# PocaFilter.net
KiCad netlist of a schematic drawn in EAGLE
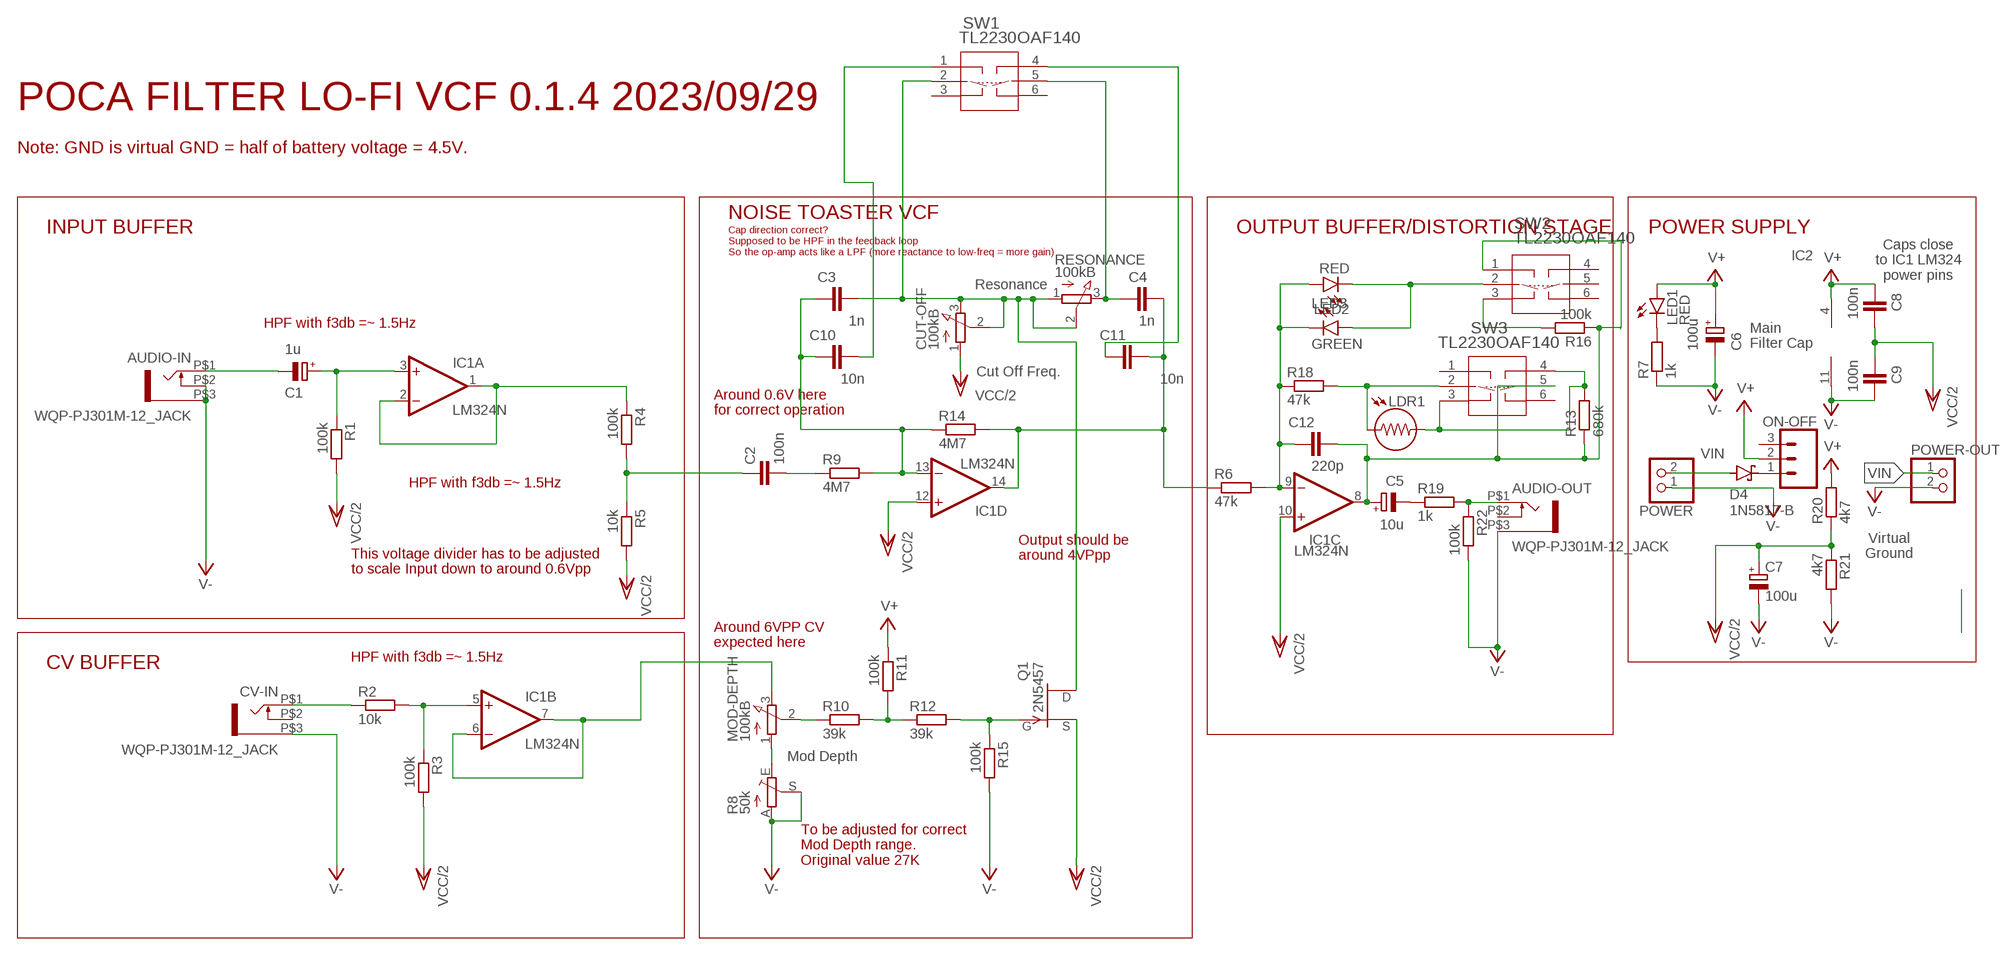
[diagram p0: schematic, sheet 1]

(export (version "E")
  (design (tool "Eeschema 10.0.6"))
  (components
    (comp (ref "AUDIO-IN")
      (value "WQP-PJ301M-12_JACK")
      (footprint "eagle-import:WQP-PJ301M-12_JACK")
      (libsource (lib "eagle-import") (part "WQP-PJ301M-12_JACK"))
    )
    (comp (ref "AUDIO-OUT")
      (value "WQP-PJ301M-12_JACK")
      (footprint "eagle-import:WQP-PJ301M-12_JACK")
      (libsource (lib "eagle-import") (part "WQP-PJ301M-12_JACK"))
    )
    (comp (ref "C1")
      (value "1u")
      (footprint "eagle-import:E2,5-6")
      (libsource (lib "eagle-import") (part "CPOL-EUE2.5-6"))
    )
    (comp (ref "C2")
      (value "100n")
      (footprint "eagle-import:C050-030X075")
      (libsource (lib "eagle-import") (part "C-EU050-030X075"))
    )
    (comp (ref "C3")
      (value "1n")
      (footprint "eagle-import:C050-030X075")
      (libsource (lib "eagle-import") (part "C-EU050-030X075"))
    )
    (comp (ref "C4")
      (value "1n")
      (footprint "eagle-import:C050-030X075")
      (libsource (lib "eagle-import") (part "C-EU050-030X075"))
    )
    (comp (ref "C5")
      (value "10u")
      (footprint "eagle-import:E2,5-6")
      (libsource (lib "eagle-import") (part "CPOL-EUE2.5-6"))
    )
    (comp (ref "C6")
      (value "100u")
      (footprint "eagle-import:E2,5-6")
      (libsource (lib "eagle-import") (part "CPOL-EUE2.5-6"))
    )
    (comp (ref "C7")
      (value "100u")
      (footprint "eagle-import:E2,5-6E")
      (libsource (lib "eagle-import") (part "CPOL-EUE2,5-6E"))
    )
    (comp (ref "C8")
      (value "100n")
      (footprint "eagle-import:C025-025X050")
      (libsource (lib "eagle-import") (part "C-EU025-025X050"))
    )
    (comp (ref "C9")
      (value "100n")
      (footprint "eagle-import:C025-025X050")
      (libsource (lib "eagle-import") (part "C-EU025-025X050"))
    )
    (comp (ref "C10")
      (value "10n")
      (footprint "eagle-import:C050-030X075")
      (libsource (lib "eagle-import") (part "C-EU050-030X075"))
    )
    (comp (ref "C11")
      (value "10n")
      (footprint "eagle-import:C050-030X075")
      (libsource (lib "eagle-import") (part "C-EU050-030X075"))
    )
    (comp (ref "C12")
      (value "220p")
      (footprint "eagle-import:C025-025X050")
      (libsource (lib "eagle-import") (part "C-EU025-025X050"))
    )
    (comp (ref "CUT-OFF")
      (value "100kB")
      (footprint "eagle-import:EVUFXM")
      (libsource (lib "eagle-import") (part "EVUMF3"))
    )
    (comp (ref "CV-IN")
      (value "WQP-PJ301M-12_JACK")
      (footprint "eagle-import:WQP-PJ301M-12_JACK")
      (libsource (lib "eagle-import") (part "WQP-PJ301M-12_JACK"))
    )
    (comp (ref "D4")
      (value "1N5817-B")
      (footprint "eagle-import:DO41-7.6")
      (libsource (lib "eagle-import") (part "1N5817-B"))
    )
    (comp (ref "IC1")
      (value "LM324N")
      (footprint "eagle-import:DIL14")
      (libsource (lib "eagle-import") (part "LM324N"))
    )
    (comp (ref "LDR1")
      (value "LDR5MM")
      (footprint "eagle-import:LDR338-54C")
      (libsource (lib "eagle-import") (part "LDR5MM"))
    )
    (comp (ref "LED1")
      (value "RED")
      (footprint "eagle-import:LED3MM")
      (libsource (lib "eagle-import") (part "led_259_LED3MM"))
    )
    (comp (ref "LED2")
      (value "RED")
      (footprint "eagle-import:LED_3MM")
      (libsource (lib "eagle-import") (part "LED3MM"))
    )
    (comp (ref "LED3")
      (value "GREEN")
      (footprint "eagle-import:LED_3MM")
      (libsource (lib "eagle-import") (part "LED3MM"))
    )
    (comp (ref "MOD-DEPTH")
      (value "100kB")
      (footprint "eagle-import:EVUFXM")
      (libsource (lib "eagle-import") (part "EVUMF3"))
    )
    (comp (ref "ON-OFF")
      (value "CONN_03LOCK")
      (footprint "eagle-import:1X03_LOCK")
      (libsource (lib "eagle-import") (part "CONN_03LOCK"))
    )
    (comp (ref "POWER")
      (value "PINHD-1X2")
      (footprint "eagle-import:1X02")
      (libsource (lib "eagle-import") (part "PINHD-1X2"))
    )
    (comp (ref "POWER-OUT")
      (value "PINHD-1X2")
      (footprint "eagle-import:1X02")
      (libsource (lib "eagle-import") (part "PINHD-1X2"))
    )
    (comp (ref "Q1")
      (value "2N5457")
      (footprint "eagle-import:TO92")
      (libsource (lib "eagle-import") (part "?20J1"))
    )
    (comp (ref "R1")
      (value "100k")
      (footprint "eagle-import:0207_10")
      (libsource (lib "eagle-import") (part "R-EU_0207/10"))
    )
    (comp (ref "R2")
      (value "10k")
      (footprint "eagle-import:0207_10")
      (libsource (lib "eagle-import") (part "R-EU_0207/10"))
    )
    (comp (ref "R3")
      (value "100k")
      (footprint "eagle-import:0207_10")
      (libsource (lib "eagle-import") (part "R-EU_0207/10"))
    )
    (comp (ref "R4")
      (value "100k")
      (footprint "eagle-import:0207_10")
      (libsource (lib "eagle-import") (part "R-EU_0207/10"))
    )
    (comp (ref "R5")
      (value "10k")
      (footprint "eagle-import:0207_10")
      (libsource (lib "eagle-import") (part "R-EU_0207/10"))
    )
    (comp (ref "R6")
      (value "47k")
      (footprint "eagle-import:0207_10")
      (libsource (lib "eagle-import") (part "R-EU_0207/10"))
    )
    (comp (ref "R7")
      (value "1k")
      (footprint "eagle-import:0207_10")
      (libsource (lib "eagle-import") (part "R-EU_0207/10"))
    )
    (comp (ref "R8")
      (value "50k")
      (footprint "eagle-import:CA6V")
      (libsource (lib "eagle-import") (part "TRIM_EU-CA6V"))
    )
    (comp (ref "R9")
      (value "4M7")
      (footprint "eagle-import:0207_10")
      (libsource (lib "eagle-import") (part "R-EU_0207/10"))
    )
    (comp (ref "R10")
      (value "39k")
      (footprint "eagle-import:0207_10")
      (libsource (lib "eagle-import") (part "R-EU_0207/10"))
    )
    (comp (ref "R11")
      (value "100k")
      (footprint "eagle-import:0207_10")
      (libsource (lib "eagle-import") (part "R-EU_0207/10"))
    )
    (comp (ref "R12")
      (value "39k")
      (footprint "eagle-import:0207_10")
      (libsource (lib "eagle-import") (part "R-EU_0207/10"))
    )
    (comp (ref "R13")
      (value "680k")
      (footprint "eagle-import:0207_10")
      (libsource (lib "eagle-import") (part "R-EU_0207/10"))
    )
    (comp (ref "R14")
      (value "4M7")
      (footprint "eagle-import:0207_10")
      (libsource (lib "eagle-import") (part "R-EU_0207/10"))
    )
    (comp (ref "R15")
      (value "100k")
      (footprint "eagle-import:0207_10")
      (libsource (lib "eagle-import") (part "R-EU_0207/10"))
    )
    (comp (ref "R16")
      (value "100k")
      (footprint "eagle-import:0204_7")
      (libsource (lib "eagle-import") (part "R-EU_0204/7"))
    )
    (comp (ref "R18")
      (value "47k")
      (footprint "eagle-import:0207_10")
      (libsource (lib "eagle-import") (part "R-EU_0207/10"))
    )
    (comp (ref "R19")
      (value "1k")
      (footprint "eagle-import:0207_10")
      (libsource (lib "eagle-import") (part "R-EU_0207/10"))
    )
    (comp (ref "R20")
      (value "4k7")
      (footprint "eagle-import:0207_10")
      (libsource (lib "eagle-import") (part "R-EU_0207/10"))
    )
    (comp (ref "R21")
      (value "4k7")
      (footprint "eagle-import:0207_10")
      (libsource (lib "eagle-import") (part "R-EU_0207/10"))
    )
    (comp (ref "R22")
      (value "100k")
      (footprint "eagle-import:0207_10")
      (libsource (lib "eagle-import") (part "R-EU_0207/10"))
    )
    (comp (ref "RESONANCE")
      (value "100kB")
      (footprint "eagle-import:EVUFXM")
      (libsource (lib "eagle-import") (part "EVUMF3"))
    )
    (comp (ref "SW1")
      (value "TL2230OAF140")
      (footprint "eagle-import:TL2230_EWI")
      (fields (field (name "COPYRIGHT") "Copyright (C) 2023 Ultra Librarian. All rights reserved."))
      (libsource (lib "eagle-import") (part "TL2230OAF140"))
    )
    (comp (ref "SW2")
      (value "TL2230OAF140")
      (footprint "eagle-import:TL2230_EWI")
      (fields (field (name "COPYRIGHT") "Copyright (C) 2023 Ultra Librarian. All rights reserved."))
      (libsource (lib "eagle-import") (part "TL2230OAF140"))
    )
    (comp (ref "SW3")
      (value "TL2230OAF140")
      (footprint "eagle-import:TL2230_EWI")
      (fields (field (name "COPYRIGHT") "Copyright (C) 2023 Ultra Librarian. All rights reserved."))
      (libsource (lib "eagle-import") (part "TL2230OAF140"))
    )
  )
  (nets
    (net (code "1") (name "Net-(AUDIO-IN-2)") (class "Default")
      (node (ref "AUDIO-IN") (pin "P$1") (pinfunction "2_P$1") (pintype "passive"))
      (node (ref "C1") (pin "-") (pinfunction "-_-") (pintype "passive"))
    )
    (net (code "2") (name "Net-(AUDIO-OUT-2)") (class "Default")
      (node (ref "AUDIO-OUT") (pin "P$1") (pinfunction "2_P$1") (pintype "passive"))
      (node (ref "R19") (pin "2") (pinfunction "2_2") (pintype "passive"))
      (node (ref "R22") (pin "1") (pinfunction "1_1") (pintype "passive"))
    )
    (net (code "3") (name "Net-(C2-Pad1)") (class "Default")
      (node (ref "C2") (pin "1") (pinfunction "1_1") (pintype "passive"))
      (node (ref "R4") (pin "2") (pinfunction "2_2") (pintype "passive"))
      (node (ref "R5") (pin "1") (pinfunction "1_1") (pintype "passive"))
    )
    (net (code "4") (name "Net-(C2-Pad2)") (class "Default")
      (node (ref "C2") (pin "2") (pinfunction "2_2") (pintype "passive"))
      (node (ref "R9") (pin "1") (pinfunction "1_1") (pintype "passive"))
    )
    (net (code "5") (name "Net-(C5-Pad-)") (class "Default")
      (node (ref "C5") (pin "-") (pinfunction "-_-") (pintype "passive"))
      (node (ref "R19") (pin "1") (pinfunction "1_1") (pintype "passive"))
    )
    (net (code "6") (name "Net-(C10-Pad2)") (class "Default")
      (node (ref "C10") (pin "2") (pinfunction "2_2") (pintype "passive"))
      (node (ref "SW1") (pin "1") (pinfunction "1_1") (pintype "passive"))
    )
    (net (code "7") (name "Net-(C11-Pad1)") (class "Default")
      (node (ref "C11") (pin "1") (pinfunction "1_1") (pintype "passive"))
      (node (ref "SW1") (pin "4") (pinfunction "4_4") (pintype "passive"))
    )
    (net (code "8") (name "Net-(CUT-OFF-E)") (class "Default")
      (node (ref "C3") (pin "2") (pinfunction "2_2") (pintype "passive"))
      (node (ref "CUT-OFF") (pin "2") (pinfunction "S_2") (pintype "passive"))
      (node (ref "CUT-OFF") (pin "3") (pinfunction "E_3") (pintype "passive"))
      (node (ref "Q1") (pin "3") (pinfunction "D_3") (pintype "passive"))
      (node (ref "RESONANCE") (pin "1") (pinfunction "A_1") (pintype "passive"))
      (node (ref "RESONANCE") (pin "2") (pinfunction "S_2") (pintype "passive"))
      (node (ref "SW1") (pin "2") (pinfunction "2_2") (pintype "passive"))
    )
    (net (code "9") (name "Net-(CV-IN-2)") (class "Default")
      (node (ref "CV-IN") (pin "P$1") (pinfunction "2_P$1") (pintype "passive"))
      (node (ref "R2") (pin "1") (pinfunction "1_1") (pintype "passive"))
    )
    (net (code "10") (name "Net-(D4-PadC)") (class "Default")
      (node (ref "D4") (pin "C") (pinfunction "C_C") (pintype "passive"))
      (node (ref "ON-OFF") (pin "1") (pinfunction "1_1") (pintype "passive"))
    )
    (net (code "11") (name "Net-(IC1A-+IN)") (class "Default")
      (node (ref "C1") (pin "+") (pinfunction "+_+") (pintype "passive"))
      (node (ref "IC1") (pin "3") (pinfunction "+IN_3") (pintype "input"))
      (node (ref "R1") (pin "1") (pinfunction "1_1") (pintype "passive"))
    )
    (net (code "12") (name "Net-(IC1A--IN)") (class "Default")
      (node (ref "IC1") (pin "1") (pinfunction "OUT_1") (pintype "output"))
      (node (ref "IC1") (pin "2") (pinfunction "-IN_2") (pintype "input"))
      (node (ref "R4") (pin "1") (pinfunction "1_1") (pintype "passive"))
    )
    (net (code "13") (name "Net-(IC1B-+IN)") (class "Default")
      (node (ref "IC1") (pin "5") (pinfunction "+IN_5") (pintype "input"))
      (node (ref "R2") (pin "2") (pinfunction "2_2") (pintype "passive"))
      (node (ref "R3") (pin "1") (pinfunction "1_1") (pintype "passive"))
    )
    (net (code "14") (name "Net-(IC1B--IN)") (class "Default")
      (node (ref "IC1") (pin "6") (pinfunction "-IN_6") (pintype "input"))
      (node (ref "IC1") (pin "7") (pinfunction "OUT_7") (pintype "output"))
      (node (ref "MOD-DEPTH") (pin "3") (pinfunction "E_3") (pintype "passive"))
    )
    (net (code "15") (name "Net-(IC1C--IN)") (class "Default")
      (node (ref "C12") (pin "1") (pinfunction "1_1") (pintype "passive"))
      (node (ref "IC1") (pin "9") (pinfunction "-IN_9") (pintype "input"))
      (node (ref "LED2") (pin "A") (pinfunction "A_A") (pintype "passive"))
      (node (ref "LED3") (pin "K") (pinfunction "C_K") (pintype "passive"))
      (node (ref "R18") (pin "1") (pinfunction "1_1") (pintype "passive"))
      (node (ref "R6") (pin "2") (pinfunction "2_2") (pintype "passive"))
    )
    (net (code "16") (name "Net-(IC1C-OUT)") (class "Default")
      (node (ref "C12") (pin "2") (pinfunction "2_2") (pintype "passive"))
      (node (ref "C5") (pin "+") (pinfunction "+_+") (pintype "passive"))
      (node (ref "IC1") (pin "8") (pinfunction "OUT_8") (pintype "output"))
      (node (ref "R13") (pin "1") (pinfunction "1_1") (pintype "passive"))
      (node (ref "R16") (pin "1") (pinfunction "1_1") (pintype "passive"))
      (node (ref "SW2") (pin "1") (pinfunction "1_1") (pintype "passive"))
      (node (ref "SW3") (pin "5") (pinfunction "5_5") (pintype "passive"))
    )
    (net (code "17") (name "Net-(IC1D--IN)") (class "Default")
      (node (ref "C10") (pin "1") (pinfunction "1_1") (pintype "passive"))
      (node (ref "C3") (pin "1") (pinfunction "1_1") (pintype "passive"))
      (node (ref "IC1") (pin "13") (pinfunction "-IN_13") (pintype "input"))
      (node (ref "R14") (pin "1") (pinfunction "1_1") (pintype "passive"))
      (node (ref "R9") (pin "2") (pinfunction "2_2") (pintype "passive"))
    )
    (net (code "18") (name "Net-(IC1D-OUT)") (class "Default")
      (node (ref "C11") (pin "2") (pinfunction "2_2") (pintype "passive"))
      (node (ref "C4") (pin "2") (pinfunction "2_2") (pintype "passive"))
      (node (ref "IC1") (pin "14") (pinfunction "OUT_14") (pintype "output"))
      (node (ref "R14") (pin "2") (pinfunction "2_2") (pintype "passive"))
      (node (ref "R6") (pin "1") (pinfunction "1_1") (pintype "passive"))
    )
    (net (code "19") (name "Net-(LDR1-Pad1)") (class "Default")
      (node (ref "LDR1") (pin "1") (pinfunction "1_1") (pintype "passive"))
      (node (ref "R18") (pin "2") (pinfunction "2_2") (pintype "passive"))
      (node (ref "SW3") (pin "2") (pinfunction "2_2") (pintype "passive"))
    )
    (net (code "20") (name "Net-(LDR1-Pad2)") (class "Default")
      (node (ref "LDR1") (pin "2") (pinfunction "2_2") (pintype "passive"))
      (node (ref "R13") (pin "2") (pinfunction "2_2") (pintype "passive"))
      (node (ref "SW3") (pin "3") (pinfunction "3_3") (pintype "passive"))
      (node (ref "SW3") (pin "4") (pinfunction "4_4") (pintype "passive"))
    )
    (net (code "21") (name "Net-(LED1-C)") (class "Default")
      (node (ref "LED1") (pin "K") (pinfunction "C_K") (pintype "passive"))
      (node (ref "R7") (pin "2") (pinfunction "2_2") (pintype "passive"))
    )
    (net (code "22") (name "Net-(LED2-C)") (class "Default")
      (node (ref "LED2") (pin "K") (pinfunction "C_K") (pintype "passive"))
      (node (ref "LED3") (pin "A") (pinfunction "A_A") (pintype "passive"))
      (node (ref "SW2") (pin "2") (pinfunction "2_2") (pintype "passive"))
    )
    (net (code "23") (name "Net-(MOD-DEPTH-A)") (class "Default")
      (node (ref "MOD-DEPTH") (pin "1") (pinfunction "A_1") (pintype "passive"))
      (node (ref "R8") (pin "E") (pinfunction "E_E") (pintype "passive"))
    )
    (net (code "24") (name "Net-(MOD-DEPTH-S)") (class "Default")
      (node (ref "MOD-DEPTH") (pin "2") (pinfunction "S_2") (pintype "passive"))
      (node (ref "R10") (pin "1") (pinfunction "1_1") (pintype "passive"))
    )
    (net (code "25") (name "Net-(Q1-G)") (class "Default")
      (node (ref "Q1") (pin "1") (pinfunction "G_1") (pintype "passive"))
      (node (ref "R12") (pin "2") (pinfunction "2_2") (pintype "passive"))
      (node (ref "R15") (pin "1") (pinfunction "1_1") (pintype "passive"))
    )
    (net (code "26") (name "Net-(R10-Pad2)") (class "Default")
      (node (ref "R10") (pin "2") (pinfunction "2_2") (pintype "passive"))
      (node (ref "R11") (pin "2") (pinfunction "2_2") (pintype "passive"))
      (node (ref "R12") (pin "1") (pinfunction "1_1") (pintype "passive"))
    )
    (net (code "27") (name "Net-(R16-Pad2)") (class "Default")
      (node (ref "R16") (pin "2") (pinfunction "2_2") (pintype "passive"))
      (node (ref "SW2") (pin "3") (pinfunction "3_3") (pintype "passive"))
    )
    (net (code "28") (name "Net-(RESONANCE-E)") (class "Default")
      (node (ref "C4") (pin "1") (pinfunction "1_1") (pintype "passive"))
      (node (ref "RESONANCE") (pin "3") (pinfunction "E_3") (pintype "passive"))
      (node (ref "SW1") (pin "5") (pinfunction "5_5") (pintype "passive"))
    )
    (net (code "29") (name "V+") (class "Default")
      (node (ref "C6") (pin "+") (pinfunction "+_+") (pintype "passive"))
      (node (ref "C8") (pin "1") (pinfunction "1_1") (pintype "passive"))
      (node (ref "IC1") (pin "4") (pinfunction "V+_4") (pintype "power_in"))
      (node (ref "LED1") (pin "A") (pinfunction "A_A") (pintype "passive"))
      (node (ref "ON-OFF") (pin "2") (pinfunction "2_2") (pintype "passive"))
      (node (ref "R11") (pin "1") (pinfunction "1_1") (pintype "passive"))
      (node (ref "R20") (pin "2") (pinfunction "2_2") (pintype "passive"))
    )
    (net (code "30") (name "V-") (class "Default")
      (node (ref "AUDIO-IN") (pin "P$2") (pinfunction "3_P$2") (pintype "passive"))
      (node (ref "AUDIO-IN") (pin "P$3") (pinfunction "1_P$3") (pintype "passive"))
      (node (ref "AUDIO-OUT") (pin "P$3") (pinfunction "1_P$3") (pintype "passive"))
      (node (ref "C6") (pin "-") (pinfunction "-_-") (pintype "passive"))
      (node (ref "C7") (pin "-") (pinfunction "-_-") (pintype "passive"))
      (node (ref "C9") (pin "2") (pinfunction "2_2") (pintype "passive"))
      (node (ref "CV-IN") (pin "P$3") (pinfunction "1_P$3") (pintype "passive"))
      (node (ref "IC1") (pin "11") (pinfunction "V-_11") (pintype "power_in"))
      (node (ref "POWER") (pin "1") (pinfunction "1_1") (pintype "passive"))
      (node (ref "POWER-OUT") (pin "2") (pinfunction "2_2") (pintype "passive"))
      (node (ref "R15") (pin "2") (pinfunction "2_2") (pintype "passive"))
      (node (ref "R21") (pin "2") (pinfunction "2_2") (pintype "passive"))
      (node (ref "R22") (pin "2") (pinfunction "2_2") (pintype "passive"))
      (node (ref "R7") (pin "1") (pinfunction "1_1") (pintype "passive"))
      (node (ref "R8") (pin "A") (pinfunction "A_A") (pintype "passive"))
      (node (ref "R8") (pin "S") (pinfunction "S_S") (pintype "passive"))
    )
    (net (code "31") (name "VCC{slash}2") (class "Default")
      (node (ref "C7") (pin "+") (pinfunction "+_+") (pintype "passive"))
      (node (ref "C8") (pin "2") (pinfunction "2_2") (pintype "passive"))
      (node (ref "C9") (pin "1") (pinfunction "1_1") (pintype "passive"))
      (node (ref "CUT-OFF") (pin "1") (pinfunction "A_1") (pintype "passive"))
      (node (ref "IC1") (pin "10") (pinfunction "+IN_10") (pintype "input"))
      (node (ref "IC1") (pin "12") (pinfunction "+IN_12") (pintype "input"))
      (node (ref "Q1") (pin "2") (pinfunction "S_2") (pintype "passive"))
      (node (ref "R1") (pin "2") (pinfunction "2_2") (pintype "passive"))
      (node (ref "R20") (pin "1") (pinfunction "1_1") (pintype "passive"))
      (node (ref "R21") (pin "1") (pinfunction "1_1") (pintype "passive"))
      (node (ref "R3") (pin "2") (pinfunction "2_2") (pintype "passive"))
      (node (ref "R5") (pin "2") (pinfunction "2_2") (pintype "passive"))
    )
    (net (code "32") (name "VIN") (class "Default")
      (node (ref "D4") (pin "A") (pinfunction "A_A") (pintype "passive"))
      (node (ref "POWER") (pin "2") (pinfunction "2_2") (pintype "passive"))
      (node (ref "POWER-OUT") (pin "1") (pinfunction "1_1") (pintype "passive"))
    )
    (net (code "33") (name "unconnected-(AUDIO-OUT-3-PadP$2)") (class "Default")
      (node (ref "AUDIO-OUT") (pin "P$2") (pinfunction "3_P$2") (pintype "passive"))
    )
    (net (code "34") (name "unconnected-(CV-IN-3-PadP$2)") (class "Default")
      (node (ref "CV-IN") (pin "P$2") (pinfunction "3_P$2") (pintype "passive"))
    )
    (net (code "35") (name "unconnected-(ON-OFF-Pad3)") (class "Default")
      (node (ref "ON-OFF") (pin "3") (pinfunction "3_3") (pintype "passive"))
    )
    (net (code "36") (name "unconnected-(SW1-Pad3)") (class "Default")
      (node (ref "SW1") (pin "3") (pinfunction "3_3") (pintype "passive"))
    )
    (net (code "37") (name "unconnected-(SW1-Pad6)") (class "Default")
      (node (ref "SW1") (pin "6") (pinfunction "6_6") (pintype "passive"))
    )
    (net (code "38") (name "unconnected-(SW2-Pad4)") (class "Default")
      (node (ref "SW2") (pin "4") (pinfunction "4_4") (pintype "passive"))
    )
    (net (code "39") (name "unconnected-(SW2-Pad5)") (class "Default")
      (node (ref "SW2") (pin "5") (pinfunction "5_5") (pintype "passive"))
    )
    (net (code "40") (name "unconnected-(SW2-Pad6)") (class "Default")
      (node (ref "SW2") (pin "6") (pinfunction "6_6") (pintype "passive"))
    )
    (net (code "41") (name "unconnected-(SW3-Pad1)") (class "Default")
      (node (ref "SW3") (pin "1") (pinfunction "1_1") (pintype "passive"))
    )
    (net (code "42") (name "unconnected-(SW3-Pad6)") (class "Default")
      (node (ref "SW3") (pin "6") (pinfunction "6_6") (pintype "passive"))
    )
  )
)
